# wwdt.net
KiCad netlist of a schematic drawn in Altium Designer
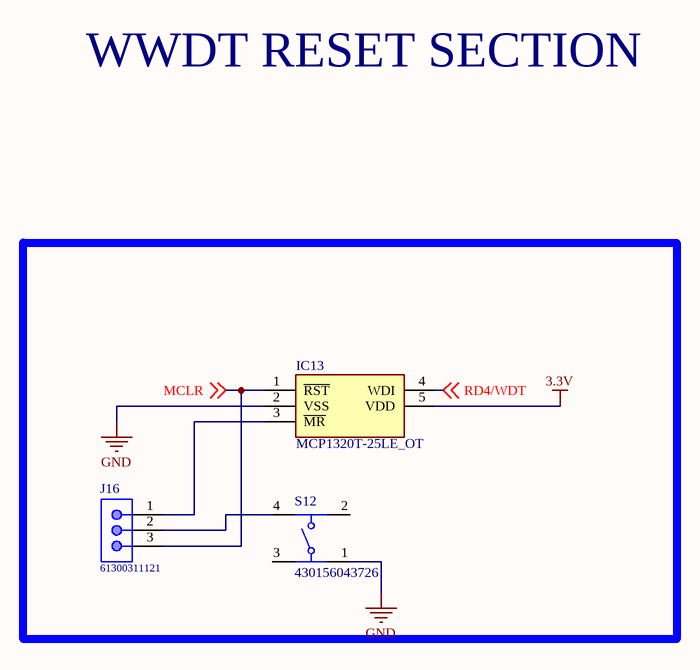
[diagram p0: wwdt.SchDoc]

(export (version "E")
  (design (tool "Eeschema 10.0.6"))
  (components
    (comp (ref "IC13")
      (value "MCP1320T-25LE_OT")
      (footprint "SamacSys:SOT95P270X145-5N")
      (description "Integrated Circuit")
      (fields
        (field (name "MANUFACTURER_PART_NUMBER") "MCP1320T-25LE/OT")
        (field (name "MOUSER PART NUMBER") "579-MCP1320T-25LE/OT")
      )
      (libsource (lib "*") (part "MCP1320T-25LE_OT"))
    )
    (comp (ref "J16")
      (value "61300311121")
      (footprint "61300311121")
      (description "WR-PHD Pin Header, THT, pitch 2.54mm, Single Row, Vertical, 3pin")
      (fields (field (name "PUBLISHER") "Wurth Elektronik"))
      (libsource (lib "SIL_Connectors WR-PHD_rev19a") (part "61300311121"))
    )
    (comp (ref "S12")
      (value "430156043726")
      (footprint "4301x60437x6")
      (description "WS-TATV THT Tact Switch 6x6mm, height 4.3mm, 260gf")
      (fields (field (name "PUBLISHER") "Wurth Elektronik"))
      (libsource (lib "Push buttons through hole_Altium_WS-TATV_rev19a") (part "430156043726"))
    )
  )
  (nets
    (net (code "1") (name "3.3V") (class "Default")
      (node (ref "IC13") (pin "5") (pinfunction "VDD_5") (pintype "passive"))
    )
    (net (code "2") (name "GND") (class "Default")
      (node (ref "IC13") (pin "2") (pinfunction "VSS_2") (pintype "passive"))
      (node (ref "S12") (pin "1") (pinfunction "1_1") (pintype "passive"))
    )
    (net (code "3") (name "MCLR") (class "Default")
      (node (ref "IC13") (pin "1") (pinfunction "~{RST}_1") (pintype "passive"))
      (node (ref "J16") (pin "3") (pinfunction "3_3") (pintype "passive"))
    )
    (net (code "4") (name "Net-(IC13-~{MR})") (class "Default")
      (node (ref "IC13") (pin "3") (pinfunction "~{MR}_3") (pintype "passive"))
      (node (ref "J16") (pin "1") (pinfunction "1_1") (pintype "passive"))
    )
    (net (code "5") (name "Net-(J16-Pad2)") (class "Default")
      (node (ref "J16") (pin "2") (pinfunction "2_2") (pintype "passive"))
      (node (ref "S12") (pin "4") (pinfunction "4_4") (pintype "passive"))
    )
    (net (code "6") (name "RD4{slash}WDT") (class "Default")
      (node (ref "IC13") (pin "4") (pinfunction "WDI_4") (pintype "passive"))
    )
    (net (code "7") (name "unconnected-(S12-Pad2)") (class "Default")
      (node (ref "S12") (pin "2") (pinfunction "2_2") (pintype "passive"))
    )
    (net (code "8") (name "unconnected-(S12-Pad3)") (class "Default")
      (node (ref "S12") (pin "3") (pinfunction "3_3") (pintype "passive"))
    )
  )
)
